# xbee_carrier.net
KiCad netlist of a schematic drawn in EAGLE
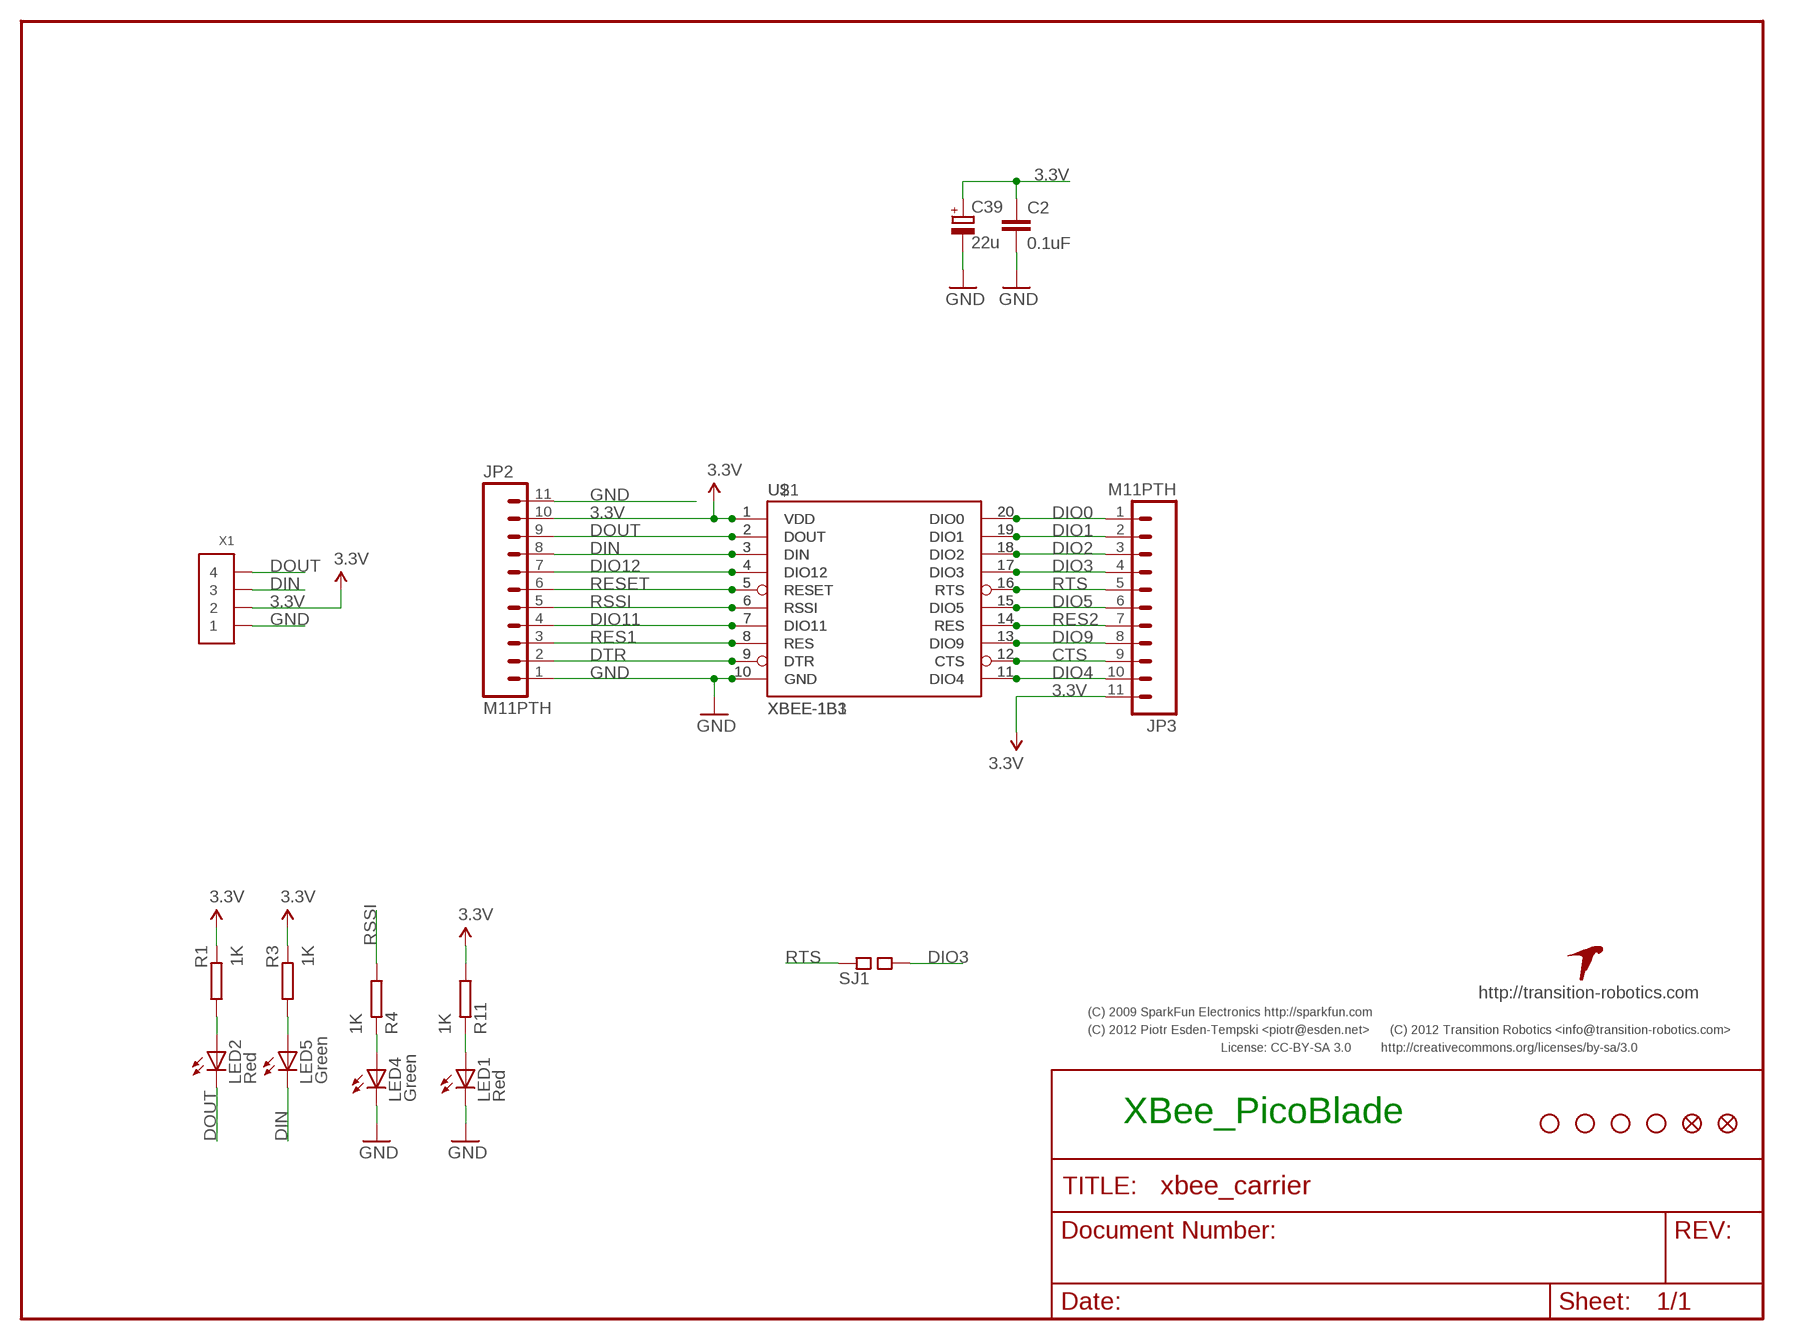
[diagram p0: schematic, sheet 1]

(export (version "E")
  (design (tool "Eeschema 10.0.6"))
  (components
    (comp (ref "C2")
      (value "0.1uF")
      (footprint "eagle-import:0402-CAP")
      (fields (field (name "PARTNO") "cap-cer-0402-100n"))
      (libsource (lib "eagle-import") (part "CAPACITOR-0402"))
    )
    (comp (ref "C39")
      (value "22u")
      (footprint "eagle-import:3528_B")
      (fields (field (name "PARTNO") "cap-tan-B-22u-16v"))
      (libsource (lib "eagle-import") (part "CAPACITOR-POLB"))
    )
    (comp (ref "JP2")
      (value "M11PTH")
      (footprint "eagle-import:1X11")
      (libsource (lib "eagle-import") (part "M11PTH"))
    )
    (comp (ref "JP3")
      (value "M11PTH")
      (footprint "eagle-import:1X11")
      (libsource (lib "eagle-import") (part "M11PTH"))
    )
    (comp (ref "LED1")
      (value "Red")
      (footprint "eagle-import:0402-LED")
      (fields (field (name "PARTNO") "led-0402-red"))
      (libsource (lib "eagle-import") (part "LED-0402"))
    )
    (comp (ref "LED2")
      (value "Red")
      (footprint "eagle-import:0402-LED")
      (fields (field (name "PARTNO") "led-0402-red"))
      (libsource (lib "eagle-import") (part "LED-0402"))
    )
    (comp (ref "LED4")
      (value "Green")
      (footprint "eagle-import:0402-LED")
      (fields (field (name "PARTNO") "led-0402-green"))
      (libsource (lib "eagle-import") (part "LED-0402"))
    )
    (comp (ref "LED5")
      (value "Green")
      (footprint "eagle-import:0402-LED")
      (fields (field (name "PARTNO") "led-0402-green"))
      (libsource (lib "eagle-import") (part "LED-0402"))
    )
    (comp (ref "R1")
      (value "1K")
      (footprint "eagle-import:0402-RES")
      (fields (field (name "PARTNO") "res-0402-1k5"))
      (libsource (lib "eagle-import") (part "RESISTOR-0402"))
    )
    (comp (ref "R3")
      (value "1K")
      (footprint "eagle-import:0402-RES")
      (fields (field (name "PARTNO") "res-0402-1k5"))
      (libsource (lib "eagle-import") (part "RESISTOR-0402"))
    )
    (comp (ref "R4")
      (value "1K")
      (footprint "eagle-import:0402-RES")
      (fields (field (name "PARTNO") "res-0402-1k5"))
      (libsource (lib "eagle-import") (part "RESISTOR-0402"))
    )
    (comp (ref "R11")
      (value "1K")
      (footprint "eagle-import:0402-RES")
      (fields (field (name "PARTNO") "res-0402-1k5"))
      (libsource (lib "eagle-import") (part "RESISTOR-0402"))
    )
    (comp (ref "SJ1")
      (value "SQ_JMP-0402")
      (footprint "eagle-import:0402-SQJMP")
      (libsource (lib "eagle-import") (part "SQ_JMP-0402"))
    )
    (comp (ref "U$1")
      (value "XBEE-1B1")
      (footprint "eagle-import:XBEE-1")
      (libsource (lib "eagle-import") (part "SparkFun-RF_XBEE-1B1"))
    )
    (comp (ref "U$2")
      (value "TR-LOGO")
      (footprint "eagle-import:TR-LOGO")
      (libsource (lib "eagle-import") (part "TR-LOGO"))
    )
    (comp (ref "U$5")
      (value "STAND-OFF")
      (footprint "eagle-import:STAND-OFF")
      (libsource (lib "eagle-import") (part "STAND-OFF"))
    )
    (comp (ref "U$7")
      (value "FIDUCIAL1X2")
      (footprint "eagle-import:FIDUCIAL-1X2")
      (libsource (lib "eagle-import") (part "FIDUCIAL1X2"))
    )
    (comp (ref "U$9")
      (value "STAND-OFF")
      (footprint "eagle-import:STAND-OFF")
      (libsource (lib "eagle-import") (part "STAND-OFF"))
    )
    (comp (ref "U$10")
      (value "STAND-OFF")
      (footprint "eagle-import:STAND-OFF")
      (libsource (lib "eagle-import") (part "STAND-OFF"))
    )
    (comp (ref "U$11")
      (value "STAND-OFF")
      (footprint "eagle-import:STAND-OFF")
      (libsource (lib "eagle-import") (part "STAND-OFF"))
    )
    (comp (ref "U$16")
      (value "FIDUCIAL1X2")
      (footprint "eagle-import:FIDUCIAL-1X2")
      (libsource (lib "eagle-import") (part "FIDUCIAL1X2"))
    )
    (comp (ref "U2")
      (value "XBEE-1B3")
      (footprint "eagle-import:XBEE-SMD")
      (libsource (lib "eagle-import") (part "XBEE-1B3"))
    )
    (comp (ref "X1")
      (value "CONN_4-1-53261")
      (footprint "eagle-import:PB-53261-04")
      (fields (field (name "PARTNO") "conn-picoblade-smd-0.05in-4"))
      (libsource (lib "eagle-import") (part "CONN_4-1-53261"))
    )
  )
  (nets
    (net (code "1") (name "/CTS") (class "Default")
      (node (ref "JP3") (pin "9") (pinfunction "9_9") (pintype "passive"))
      (node (ref "U$1") (pin "12") (pinfunction "CTS_12") (pintype "output"))
      (node (ref "U2") (pin "12") (pinfunction "CTS_12") (pintype "output"))
    )
    (net (code "2") (name "/DIN") (class "Default")
      (node (ref "JP2") (pin "8") (pinfunction "8_8") (pintype "passive"))
      (node (ref "LED5") (pin "C") (pinfunction "C_C") (pintype "passive"))
      (node (ref "U$1") (pin "3") (pinfunction "DIN_3") (pintype "input"))
      (node (ref "U2") (pin "3") (pinfunction "DIN_3") (pintype "input"))
      (node (ref "X1") (pin "3") (pinfunction "3_3") (pintype "bidirectional"))
    )
    (net (code "3") (name "/DIO0") (class "Default")
      (node (ref "JP3") (pin "1") (pinfunction "1_1") (pintype "passive"))
      (node (ref "U$1") (pin "20") (pinfunction "DIO0_20") (pintype "bidirectional"))
      (node (ref "U2") (pin "20") (pinfunction "DIO0_20") (pintype "bidirectional"))
    )
    (net (code "4") (name "/DIO1") (class "Default")
      (node (ref "JP3") (pin "2") (pinfunction "2_2") (pintype "passive"))
      (node (ref "U$1") (pin "19") (pinfunction "DIO1_19") (pintype "bidirectional"))
      (node (ref "U2") (pin "19") (pinfunction "DIO1_19") (pintype "bidirectional"))
    )
    (net (code "5") (name "/DIO2") (class "Default")
      (node (ref "JP3") (pin "3") (pinfunction "3_3") (pintype "passive"))
      (node (ref "U$1") (pin "18") (pinfunction "DIO2_18") (pintype "bidirectional"))
      (node (ref "U2") (pin "18") (pinfunction "DIO2_18") (pintype "bidirectional"))
    )
    (net (code "6") (name "/DIO3") (class "Default")
      (node (ref "JP3") (pin "4") (pinfunction "4_4") (pintype "passive"))
      (node (ref "SJ1") (pin "P$2") (pinfunction "2_P$2") (pintype "passive"))
      (node (ref "U$1") (pin "17") (pinfunction "DIO3_17") (pintype "bidirectional"))
      (node (ref "U2") (pin "17") (pinfunction "DIO3_17") (pintype "bidirectional"))
    )
    (net (code "7") (name "/DIO4") (class "Default")
      (node (ref "JP3") (pin "10") (pinfunction "10_10") (pintype "passive"))
      (node (ref "U$1") (pin "11") (pinfunction "DIO4_11") (pintype "bidirectional"))
      (node (ref "U2") (pin "11") (pinfunction "DIO4_11") (pintype "bidirectional"))
    )
    (net (code "8") (name "/DIO5") (class "Default")
      (node (ref "JP3") (pin "6") (pinfunction "6_6") (pintype "passive"))
      (node (ref "U$1") (pin "15") (pinfunction "DIO5_15") (pintype "bidirectional"))
      (node (ref "U2") (pin "15") (pinfunction "DIO5_15") (pintype "bidirectional"))
    )
    (net (code "9") (name "/DIO9") (class "Default")
      (node (ref "JP3") (pin "8") (pinfunction "8_8") (pintype "passive"))
      (node (ref "U$1") (pin "13") (pinfunction "DIO9_13") (pintype "bidirectional"))
      (node (ref "U2") (pin "13") (pinfunction "DIO9_13") (pintype "bidirectional"))
    )
    (net (code "10") (name "/DIO11") (class "Default")
      (node (ref "JP2") (pin "4") (pinfunction "4_4") (pintype "passive"))
      (node (ref "U$1") (pin "7") (pinfunction "DIO11_7") (pintype "bidirectional"))
      (node (ref "U2") (pin "7") (pinfunction "DIO11_7") (pintype "bidirectional"))
    )
    (net (code "11") (name "/DIO12") (class "Default")
      (node (ref "JP2") (pin "7") (pinfunction "7_7") (pintype "passive"))
      (node (ref "U$1") (pin "4") (pinfunction "DIO12_4") (pintype "bidirectional"))
      (node (ref "U2") (pin "4") (pinfunction "DIO12_4") (pintype "bidirectional"))
    )
    (net (code "12") (name "/DOUT") (class "Default")
      (node (ref "JP2") (pin "9") (pinfunction "9_9") (pintype "passive"))
      (node (ref "LED2") (pin "C") (pinfunction "C_C") (pintype "passive"))
      (node (ref "U$1") (pin "2") (pinfunction "DOUT_2") (pintype "output"))
      (node (ref "U2") (pin "2") (pinfunction "DOUT_2") (pintype "output"))
      (node (ref "X1") (pin "4") (pinfunction "4_4") (pintype "bidirectional"))
    )
    (net (code "13") (name "/DTR") (class "Default")
      (node (ref "JP2") (pin "2") (pinfunction "2_2") (pintype "passive"))
      (node (ref "U$1") (pin "9") (pinfunction "DTR_9") (pintype "bidirectional"))
      (node (ref "U2") (pin "9") (pinfunction "DTR_9") (pintype "bidirectional"))
    )
    (net (code "14") (name "/RES1") (class "Default")
      (node (ref "JP2") (pin "3") (pinfunction "3_3") (pintype "passive"))
      (node (ref "U$1") (pin "8") (pinfunction "RES_8") (pintype "bidirectional"))
      (node (ref "U2") (pin "8") (pinfunction "RES_8") (pintype "bidirectional"))
    )
    (net (code "15") (name "/RES2") (class "Default")
      (node (ref "JP3") (pin "7") (pinfunction "7_7") (pintype "passive"))
      (node (ref "U$1") (pin "14") (pinfunction "RES_14") (pintype "bidirectional"))
      (node (ref "U2") (pin "14") (pinfunction "RES_14") (pintype "bidirectional"))
    )
    (net (code "16") (name "/RESET") (class "Default")
      (node (ref "JP2") (pin "6") (pinfunction "6_6") (pintype "passive"))
      (node (ref "U$1") (pin "5") (pinfunction "RESET_5") (pintype "input"))
      (node (ref "U2") (pin "5") (pinfunction "RESET_5") (pintype "input"))
    )
    (net (code "17") (name "/RSSI") (class "Default")
      (node (ref "JP2") (pin "5") (pinfunction "5_5") (pintype "passive"))
      (node (ref "R4") (pin "P$2") (pinfunction "2_P$2") (pintype "passive"))
      (node (ref "U$1") (pin "6") (pinfunction "RSSI_6") (pintype "bidirectional"))
      (node (ref "U2") (pin "6") (pinfunction "RSSI_6") (pintype "bidirectional"))
    )
    (net (code "18") (name "/RTS") (class "Default")
      (node (ref "JP3") (pin "5") (pinfunction "5_5") (pintype "passive"))
      (node (ref "SJ1") (pin "P$1") (pinfunction "1_P$1") (pintype "passive"))
      (node (ref "U$1") (pin "16") (pinfunction "RTS_16") (pintype "input"))
      (node (ref "U2") (pin "16") (pinfunction "RTS_16") (pintype "input"))
    )
    (net (code "19") (name "3.3V") (class "Default")
      (node (ref "C2") (pin "P$1") (pinfunction "1_P$1") (pintype "passive"))
      (node (ref "C39") (pin "+") (pinfunction "+_+") (pintype "passive"))
      (node (ref "JP2") (pin "10") (pinfunction "10_10") (pintype "passive"))
      (node (ref "JP3") (pin "11") (pinfunction "11_11") (pintype "passive"))
      (node (ref "R1") (pin "P$1") (pinfunction "1_P$1") (pintype "passive"))
      (node (ref "R11") (pin "P$2") (pinfunction "2_P$2") (pintype "passive"))
      (node (ref "R3") (pin "P$1") (pinfunction "1_P$1") (pintype "passive"))
      (node (ref "U$1") (pin "1") (pinfunction "VDD_1") (pintype "power_in"))
      (node (ref "U2") (pin "1") (pinfunction "VDD_1") (pintype "power_in"))
      (node (ref "X1") (pin "2") (pinfunction "2_2") (pintype "bidirectional"))
    )
    (net (code "20") (name "GND") (class "Default")
      (node (ref "C2") (pin "P$2") (pinfunction "2_P$2") (pintype "passive"))
      (node (ref "C39") (pin "-") (pinfunction "-_-") (pintype "passive"))
      (node (ref "JP2") (pin "1") (pinfunction "1_1") (pintype "passive"))
      (node (ref "JP2") (pin "11") (pinfunction "11_11") (pintype "passive"))
      (node (ref "LED1") (pin "C") (pinfunction "C_C") (pintype "passive"))
      (node (ref "LED4") (pin "C") (pinfunction "C_C") (pintype "passive"))
      (node (ref "U$1") (pin "10") (pinfunction "GND_10") (pintype "power_in"))
      (node (ref "U2") (pin "10") (pinfunction "GND_10") (pintype "power_in"))
      (node (ref "X1") (pin "1") (pinfunction "1_1") (pintype "bidirectional"))
    )
    (net (code "21") (name "Net-(R1-2)") (class "Default")
      (node (ref "LED2") (pin "A") (pinfunction "A_A") (pintype "passive"))
      (node (ref "R1") (pin "P$2") (pinfunction "2_P$2") (pintype "passive"))
    )
    (net (code "22") (name "Net-(R3-2)") (class "Default")
      (node (ref "LED5") (pin "A") (pinfunction "A_A") (pintype "passive"))
      (node (ref "R3") (pin "P$2") (pinfunction "2_P$2") (pintype "passive"))
    )
    (net (code "23") (name "Net-(R4-1)") (class "Default")
      (node (ref "LED4") (pin "A") (pinfunction "A_A") (pintype "passive"))
      (node (ref "R4") (pin "P$1") (pinfunction "1_P$1") (pintype "passive"))
    )
    (net (code "24") (name "Net-(R11-1)") (class "Default")
      (node (ref "LED1") (pin "A") (pinfunction "A_A") (pintype "passive"))
      (node (ref "R11") (pin "P$1") (pinfunction "1_P$1") (pintype "passive"))
    )
  )
)
